# 28V-motor-driver.net
KiCad netlist of a schematic drawn in Altium Designer
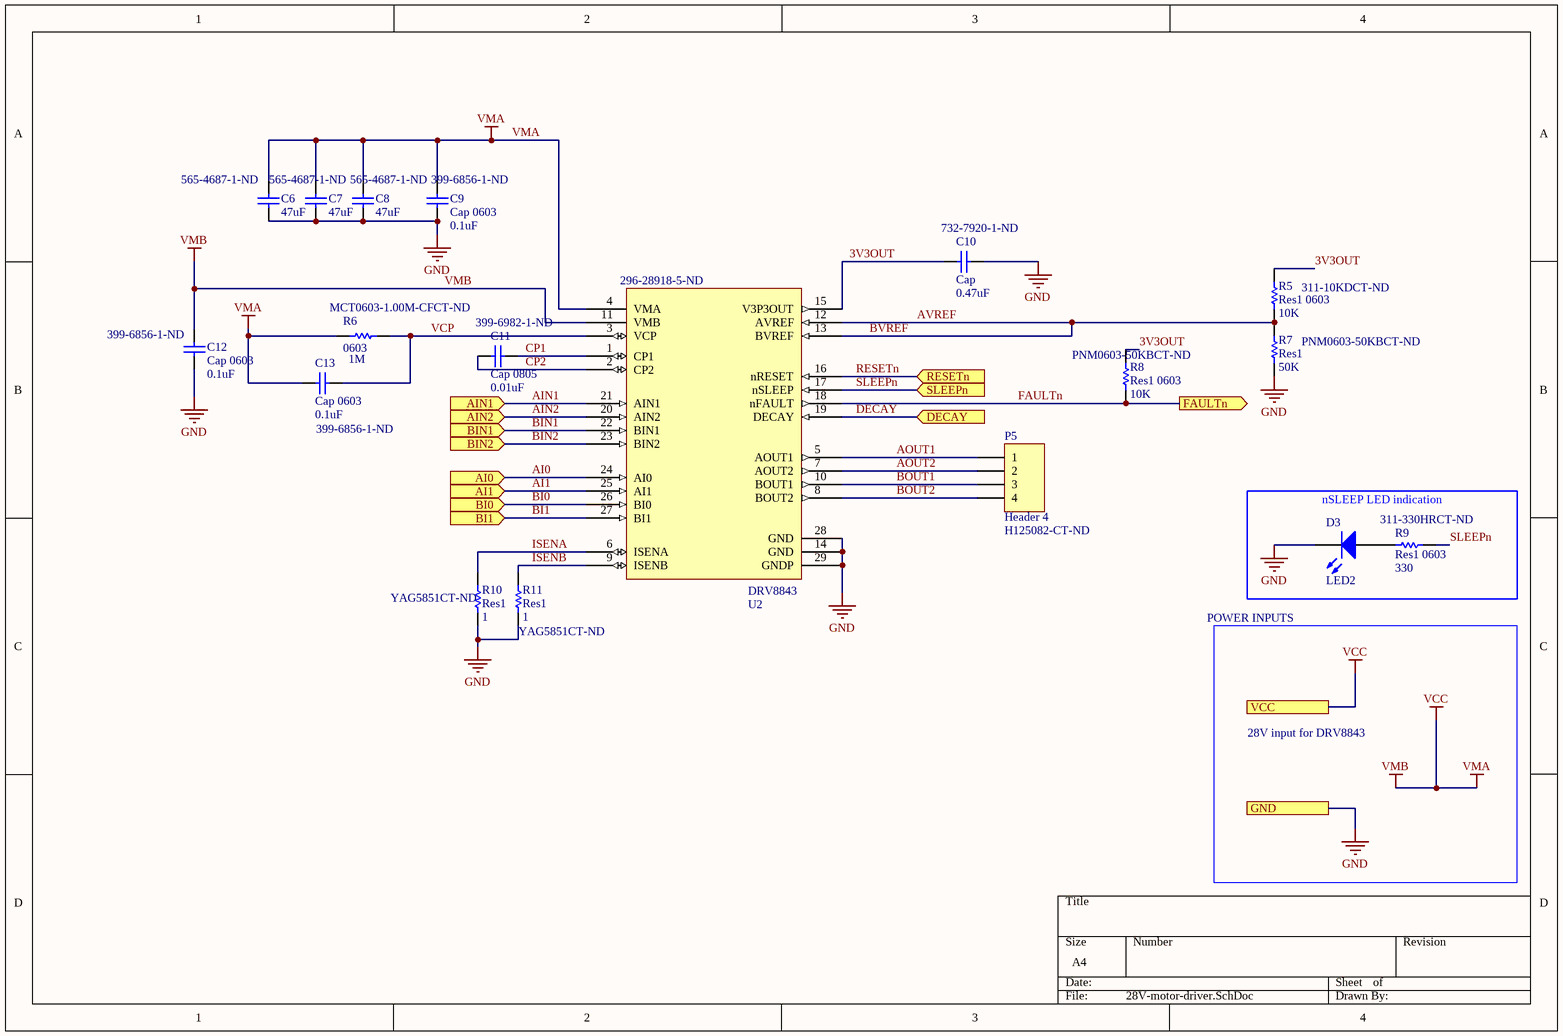
[diagram p0: 28V-motor-driver.SchDoc]

(export (version "E")
  (design (tool "Eeschema 10.0.6"))
  (components
    (comp (ref "C6")
      (value "47uF")
      (footprint "CAP-2 J-lead")
      (description "47µF ±20% 50V Ceramic Capacitor X7R Stacked SMD, 2 J-Lead")
      (fields
        (field (name "SUPPLIER PART NUMBER 1") "565-4687-1-ND")
        (field (name "PUBLISHER") "Altium Limited")
      )
      (libsource (lib "Miscellaneous Devices") (part "Cap"))
    )
    (comp (ref "C7")
      (value "47uF")
      (footprint "CAP-2 J-lead")
      (description "47µF ±20% 50V Ceramic Capacitor X7R Stacked SMD, 2 J-Lead")
      (fields
        (field (name "SUPPLIER PART NUMBER 1") "565-4687-1-ND")
        (field (name "PUBLISHER") "Altium Limited")
      )
      (libsource (lib "Miscellaneous Devices") (part "Cap"))
    )
    (comp (ref "C8")
      (value "47uF")
      (footprint "CAP-2 J-lead")
      (description "47µF ±20% 50V Ceramic Capacitor X7R Stacked SMD, 2 J-Lead")
      (fields
        (field (name "SUPPLIER PART NUMBER 1") "565-4687-1-ND")
        (field (name "PUBLISHER") "Altium Limited")
      )
      (libsource (lib "Miscellaneous Devices") (part "Cap"))
    )
    (comp (ref "C9")
      (value "Cap 0603")
      (footprint "0603-RES")
      (description "Capacitor")
      (fields
        (field (name "ALTIUM_VALUE") "0.1uF")
        (field (name "SUPPLIER PART NUMBER 1") "399-6856-1-ND")
        (field (name "PUBLISHER") "Altium Limited")
      )
      (libsource (lib "Miscellaneous Devices") (part "Cap"))
    )
    (comp (ref "C10")
      (value "Cap")
      (footprint "0603-RES")
      (description "Capacitor")
      (fields
        (field (name "ALTIUM_VALUE") "0.47uF")
        (field (name "TOLERANCE") "10%")
        (field (name "SUPPLIER PART NUMBER 1") "732-7920-1-ND")
        (field (name "PUBLISHER") "Altium Limited")
      )
      (libsource (lib "Miscellaneous Devices") (part "Cap"))
    )
    (comp (ref "C11")
      (value "Cap 0805")
      (footprint "6-0805_M")
      (description "Capacitor")
      (fields
        (field (name "ALTIUM_VALUE") "0.01uF")
        (field (name "SUPPLIER PART NUMBER 2") "399-6982-1-ND")
        (field (name "MANUFACTURER") "KEMET")
        (field (name "MANUFACTURER PART NUMBER") "C0805F103K5RACAUTO")
        (field (name "PUBLISHER") "Altium Limited")
      )
      (libsource (lib "Miscellaneous Devices") (part "Cap"))
    )
    (comp (ref "C12")
      (value "Cap 0603")
      (footprint "0603-RES")
      (description "Capacitor")
      (fields
        (field (name "ALTIUM_VALUE") "0.1uF")
        (field (name "SUPPLIER PART NUMBER 1") "399-6856-1-ND")
        (field (name "PUBLISHER") "Altium Limited")
      )
      (libsource (lib "Miscellaneous Devices") (part "Cap"))
    )
    (comp (ref "C13")
      (value "Cap 0603")
      (footprint "0603-RES")
      (description "Capacitor")
      (fields
        (field (name "ALTIUM_VALUE") "0.1uF")
        (field (name "SUPPLIER PART NUMBER 1") "399-6856-1-ND")
        (field (name "PUBLISHER") "Altium Limited")
      )
      (libsource (lib "Miscellaneous Devices") (part "Cap"))
    )
    (comp (ref "D3")
      (value "LED2")
      (footprint "0603-LED")
      (description "Typical RED, GREEN, YELLOW, AMBER GaAs LED")
      (fields (field (name "PUBLISHER") "Altium Limited"))
      (libsource (lib "Miscellaneous Devices") (part "LED2"))
    )
    (comp (ref "P5")
      (value "Header 4")
      (footprint "DF13A-4P-1.25H(51)")
      (description "Header, 4-Pin")
      (fields
        (field (name "SUPPLIER PART NUMBER 1") "H125082-CT-ND")
        (field (name "PUBLISHER") "Altium Limited")
      )
      (libsource (lib "Miscellaneous Connectors") (part "Header 4"))
    )
    (comp (ref "R5")
      (value "Res1 0603")
      (footprint "0603-RES")
      (description "Resistor")
      (fields
        (field (name "ALTIUM_VALUE") "10K")
        (field (name "SUPPLIER PART NUMBER 1") "311-10KDCT-ND")
        (field (name "MANUFACTURER") "Yageo")
        (field (name "MANUFACTURER PART NUMBER") "RT0603DRD0710KL")
        (field (name "PUBLISHER") "Altium Limited")
      )
      (libsource (lib "Miscellaneous Devices") (part "Res1"))
    )
    (comp (ref "R6")
      (value "0603")
      (footprint "0603-RES")
      (description "Resistor")
      (fields
        (field (name "ALTIUM_VALUE") "1M")
        (field (name "SUPPLIER PART NUMBER 1") "MCT0603-1.00M-CFCT-ND")
        (field (name "PUBLISHER") "Altium Limited")
      )
      (libsource (lib "Miscellaneous Devices") (part "Res1"))
    )
    (comp (ref "R7")
      (value "Res1")
      (footprint "0603-RES")
      (description "Resistor")
      (fields
        (field (name "ALTIUM_VALUE") "50K")
        (field (name "SUPPLIER PART NUMBER 1") "PNM0603-50KBCT-ND")
        (field (name "PUBLISHER") "Altium Limited")
      )
      (libsource (lib "Miscellaneous Devices") (part "Res1"))
    )
    (comp (ref "R8")
      (value "Res1 0603")
      (footprint "0603-RES")
      (description "Resistor")
      (fields
        (field (name "ALTIUM_VALUE") "10K")
        (field (name "SUPPLIER PART NUMBER 1") "PNM0603-50KBCT-ND")
        (field (name "PUBLISHER") "Altium Limited")
      )
      (libsource (lib "Miscellaneous Devices") (part "Res1"))
    )
    (comp (ref "R9")
      (value "Res1 0603")
      (footprint "0603-RES")
      (description "Resistor")
      (fields
        (field (name "ALTIUM_VALUE") "330")
        (field (name "SUPPLIER PART NUMBER 1") "311-330HRCT-ND")
        (field (name "PUBLISHER") "Altium Limited")
      )
      (libsource (lib "Miscellaneous Devices") (part "Res1"))
    )
    (comp (ref "R10")
      (value "Res1")
      (footprint "6-0805_M")
      (description "Resistor")
      (fields
        (field (name "ALTIUM_VALUE") "1")
        (field (name "SUPPLIER PART NUMBER 1") "YAG5851CT-ND")
        (field (name "PUBLISHER") "Altium Limited")
      )
      (libsource (lib "Miscellaneous Devices") (part "Res1"))
    )
    (comp (ref "R11")
      (value "Res1")
      (footprint "6-0805_M")
      (description "Resistor")
      (fields
        (field (name "ALTIUM_VALUE") "1")
        (field (name "SUPPLIER PART NUMBER 1") "YAG5851CT-ND")
        (field (name "PUBLISHER") "Altium Limited")
      )
      (libsource (lib "Miscellaneous Devices") (part "Res1"))
    )
    (comp (ref "U2")
      (value "DRV8843")
      (footprint "SOP65P640X110-29N")
      (description "Dual H-Bridge Driver, accept input voltages from 8.2V ~ 45V, with two-bit current control")
      (fields
        (field (name "SUPPLIER PART NUMBER 1") "296-28918-5-ND")
        (field (name "MANUFACTURER") "Texas Instruments")
        (field (name "MANUFACTURER PART NUMBER") "DRV8843PWP")
      )
      (libsource (lib "PAY") (part "DRV8843"))
    )
  )
  (nets
    (net (code "1") (name "/3V3OUT") (class "Default")
      (node (ref "C10") (pin "1") (pinfunction "1_1") (pintype "passive"))
      (node (ref "R5") (pin "2") (pinfunction "2_2") (pintype "passive"))
      (node (ref "R8") (pin "2") (pinfunction "2_2") (pintype "passive"))
      (node (ref "U2") (pin "15") (pinfunction "V3P3OUT_15") (pintype "output"))
    )
    (net (code "2") (name "/AI0") (class "Default")
      (node (ref "U2") (pin "24") (pinfunction "AI0_24") (pintype "input"))
    )
    (net (code "3") (name "/AI1") (class "Default")
      (node (ref "U2") (pin "25") (pinfunction "AI1_25") (pintype "input"))
    )
    (net (code "4") (name "/AIN1") (class "Default")
      (node (ref "U2") (pin "21") (pinfunction "AIN1_21") (pintype "input"))
    )
    (net (code "5") (name "/AIN2") (class "Default")
      (node (ref "U2") (pin "20") (pinfunction "AIN2_20") (pintype "input"))
    )
    (net (code "6") (name "/AOUT1") (class "Default")
      (node (ref "P5") (pin "1") (pinfunction "1_1") (pintype "passive"))
      (node (ref "U2") (pin "5") (pinfunction "AOUT1_5") (pintype "output"))
    )
    (net (code "7") (name "/AOUT2") (class "Default")
      (node (ref "P5") (pin "2") (pinfunction "2_2") (pintype "passive"))
      (node (ref "U2") (pin "7") (pinfunction "AOUT2_7") (pintype "output"))
    )
    (net (code "8") (name "/AVREF") (class "Default")
      (node (ref "R5") (pin "1") (pinfunction "1_1") (pintype "passive"))
      (node (ref "R7") (pin "2") (pinfunction "2_2") (pintype "passive"))
      (node (ref "U2") (pin "12") (pinfunction "AVREF_12") (pintype "input"))
      (node (ref "U2") (pin "13") (pinfunction "BVREF_13") (pintype "input"))
    )
    (net (code "9") (name "/BI0") (class "Default")
      (node (ref "U2") (pin "26") (pinfunction "BI0_26") (pintype "input"))
    )
    (net (code "10") (name "/BI1") (class "Default")
      (node (ref "U2") (pin "27") (pinfunction "BI1_27") (pintype "input"))
    )
    (net (code "11") (name "/BIN1") (class "Default")
      (node (ref "U2") (pin "22") (pinfunction "BIN1_22") (pintype "input"))
    )
    (net (code "12") (name "/BIN2") (class "Default")
      (node (ref "U2") (pin "23") (pinfunction "BIN2_23") (pintype "input"))
    )
    (net (code "13") (name "/BOUT1") (class "Default")
      (node (ref "P5") (pin "3") (pinfunction "3_3") (pintype "passive"))
      (node (ref "U2") (pin "10") (pinfunction "BOUT1_10") (pintype "output"))
    )
    (net (code "14") (name "/BOUT2") (class "Default")
      (node (ref "P5") (pin "4") (pinfunction "4_4") (pintype "passive"))
      (node (ref "U2") (pin "8") (pinfunction "BOUT2_8") (pintype "output"))
    )
    (net (code "15") (name "/CP1") (class "Default")
      (node (ref "C11") (pin "1") (pinfunction "1_1") (pintype "passive"))
      (node (ref "U2") (pin "1") (pinfunction "CP1_1") (pintype "bidirectional"))
    )
    (net (code "16") (name "/CP2") (class "Default")
      (node (ref "C11") (pin "2") (pinfunction "2_2") (pintype "passive"))
      (node (ref "U2") (pin "2") (pinfunction "CP2_2") (pintype "bidirectional"))
    )
    (net (code "17") (name "/DECAY") (class "Default")
      (node (ref "U2") (pin "19") (pinfunction "DECAY_19") (pintype "input"))
    )
    (net (code "18") (name "/FAULTn") (class "Default")
      (node (ref "R8") (pin "1") (pinfunction "1_1") (pintype "passive"))
      (node (ref "U2") (pin "18") (pinfunction "nFAULT_18") (pintype "output"))
    )
    (net (code "19") (name "/ISENA") (class "Default")
      (node (ref "R10") (pin "1") (pinfunction "1_1") (pintype "passive"))
      (node (ref "U2") (pin "6") (pinfunction "ISENA_6") (pintype "bidirectional"))
    )
    (net (code "20") (name "/ISENB") (class "Default")
      (node (ref "R11") (pin "1") (pinfunction "1_1") (pintype "passive"))
      (node (ref "U2") (pin "9") (pinfunction "ISENB_9") (pintype "bidirectional"))
    )
    (net (code "21") (name "/RESETn") (class "Default")
      (node (ref "U2") (pin "16") (pinfunction "nRESET_16") (pintype "input"))
    )
    (net (code "22") (name "/SLEEPn") (class "Default")
      (node (ref "R9") (pin "2") (pinfunction "2_2") (pintype "passive"))
      (node (ref "U2") (pin "17") (pinfunction "nSLEEP_17") (pintype "input"))
    )
    (net (code "23") (name "/VCP") (class "Default")
      (node (ref "C13") (pin "2") (pinfunction "2_2") (pintype "passive"))
      (node (ref "R6") (pin "2") (pinfunction "2_2") (pintype "passive"))
      (node (ref "U2") (pin "3") (pinfunction "VCP_3") (pintype "bidirectional"))
    )
    (net (code "24") (name "GND") (class "Default")
      (node (ref "C10") (pin "2") (pinfunction "2_2") (pintype "passive"))
      (node (ref "C12") (pin "2") (pinfunction "2_2") (pintype "passive"))
      (node (ref "C6") (pin "2") (pinfunction "2_2") (pintype "passive"))
      (node (ref "C7") (pin "2") (pinfunction "2_2") (pintype "passive"))
      (node (ref "C8") (pin "2") (pinfunction "2_2") (pintype "passive"))
      (node (ref "C9") (pin "2") (pinfunction "2_2") (pintype "passive"))
      (node (ref "D3") (pin "2") (pinfunction "K_2") (pintype "passive"))
      (node (ref "R10") (pin "2") (pinfunction "2_2") (pintype "passive"))
      (node (ref "R11") (pin "2") (pinfunction "2_2") (pintype "passive"))
      (node (ref "R7") (pin "1") (pinfunction "1_1") (pintype "passive"))
      (node (ref "U2") (pin "14") (pinfunction "GND_14") (pintype "power_in"))
      (node (ref "U2") (pin "28") (pinfunction "GND_28") (pintype "power_in"))
      (node (ref "U2") (pin "29") (pinfunction "GNDP_29") (pintype "power_in"))
    )
    (net (code "25") (name "Net-(D3-A)") (class "Default")
      (node (ref "D3") (pin "1") (pinfunction "A_1") (pintype "passive"))
      (node (ref "R9") (pin "1") (pinfunction "1_1") (pintype "passive"))
    )
    (net (code "26") (name "VCC") (class "Default")
      (node (ref "C12") (pin "1") (pinfunction "1_1") (pintype "passive"))
      (node (ref "C13") (pin "1") (pinfunction "1_1") (pintype "passive"))
      (node (ref "C6") (pin "1") (pinfunction "1_1") (pintype "passive"))
      (node (ref "C7") (pin "1") (pinfunction "1_1") (pintype "passive"))
      (node (ref "C8") (pin "1") (pinfunction "1_1") (pintype "passive"))
      (node (ref "C9") (pin "1") (pinfunction "1_1") (pintype "passive"))
      (node (ref "R6") (pin "1") (pinfunction "1_1") (pintype "passive"))
      (node (ref "U2") (pin "11") (pinfunction "VMB_11") (pintype "power_in"))
      (node (ref "U2") (pin "4") (pinfunction "VMA_4") (pintype "power_in"))
    )
  )
)
